# LDO-12V.net
KiCad netlist of a schematic drawn in Altium Designer
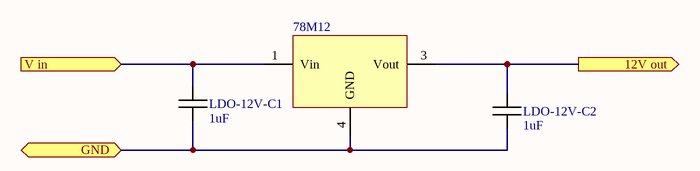
[diagram p0: LDO-12V.SchDoc]

(export (version "E")
  (design (tool "Eeschema 10.0.6"))
  (components
    (comp (ref "78M12") (value "LDO 12V") (footprint "TO-252-AA") (libsource (lib "ICs") (part "78M12")))
    (comp (ref "LDO-12V-C1")
      (value "1uF")
      (footprint "C 0805 / 2012")
      (libsource (lib "AMS1117 breakout") (part "Capacitor"))
    )
    (comp (ref "LDO-12V-C2")
      (value "1uF")
      (footprint "C 0805 / 2012")
      (libsource (lib "AMS1117 breakout") (part "Capacitor"))
    )
  )
  (nets
    (net (code "1") (name "/12V out") (class "Default")
      (node (ref "78M12") (pin "3") (pinfunction "Vout_3") (pintype "passive"))
      (node (ref "LDO-12V-C2") (pin "2") (pinfunction "2_2") (pintype "passive"))
    )
    (net (code "2") (name "/GND") (class "Default")
      (node (ref "78M12") (pin "4") (pinfunction "GND_4") (pintype "passive"))
      (node (ref "LDO-12V-C1") (pin "1") (pinfunction "1_1") (pintype "passive"))
      (node (ref "LDO-12V-C2") (pin "1") (pinfunction "1_1") (pintype "passive"))
    )
    (net (code "3") (name "/V in") (class "Default")
      (node (ref "78M12") (pin "1") (pinfunction "Vin_1") (pintype "passive"))
      (node (ref "LDO-12V-C1") (pin "2") (pinfunction "2_2") (pintype "passive"))
    )
  )
)
